# HDMI.net
KiCad netlist of a schematic drawn in Altium Designer
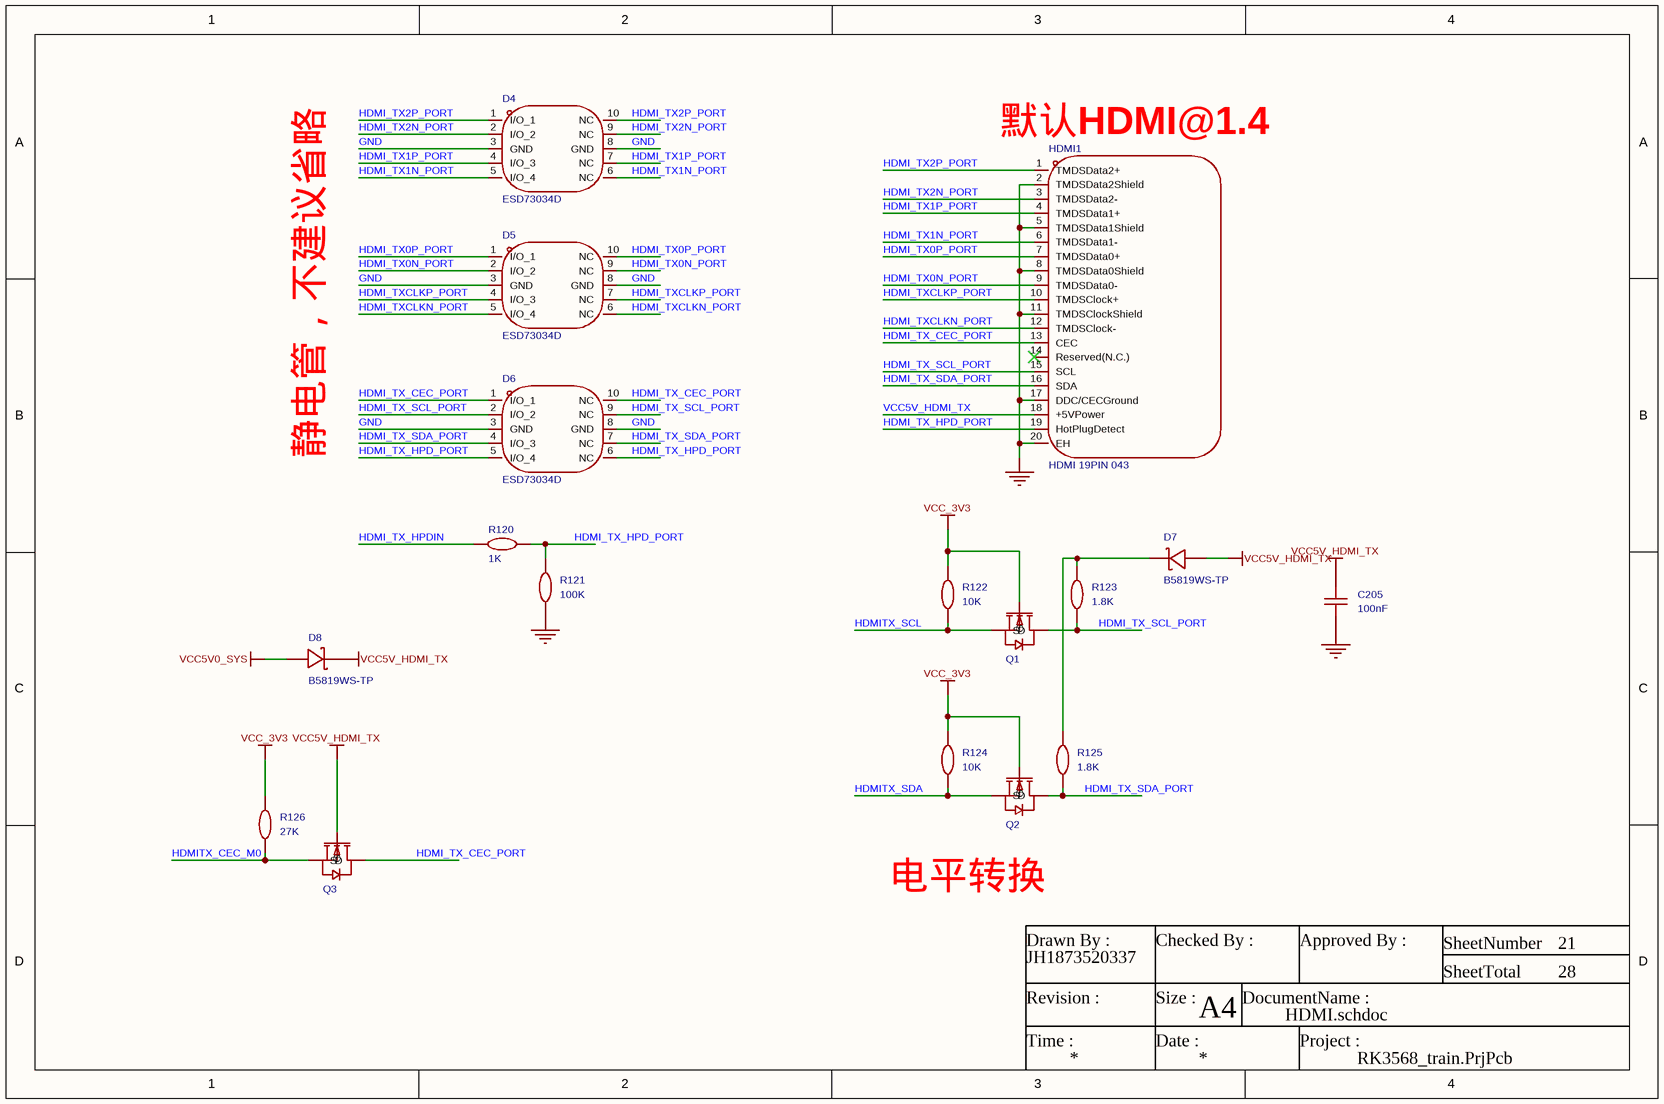
[diagram p0: HDMI.schdoc]

(export (version "E")
  (design (tool "Eeschema 10.0.6"))
  (components
    (comp (ref "C205")
      (value "100nF")
      (footprint "C0603")
      (libsource (lib "altium-import") (part "root_1_CAP_0603_"))
    )
    (comp (ref "D4")
      (value "ESD73034D")
      (footprint "DFN-10_L2.5-W1.0-P0.50-BL-2")
      (description "极性:双向;反向截止电压(Vrwm):3.3V;钳位电压:18V;峰值脉冲电流(Ipp):3A@8/20us;峰值脉冲功率(Ppp):60W@8/20us;击穿电压:8.5V;")
      (fields (field (name "MANUFACTURER") "TECH PUBLIC(台舟)"))
      (libsource (lib "altium-import") (part "root_0_ESD73034D_"))
    )
    (comp (ref "D5")
      (value "ESD73034D")
      (footprint "DFN-10_L2.5-W1.0-P0.50-BL-2")
      (description "极性:双向;反向截止电压(Vrwm):3.3V;钳位电压:18V;峰值脉冲电流(Ipp):3A@8/20us;峰值脉冲功率(Ppp):60W@8/20us;击穿电压:8.5V;")
      (fields (field (name "MANUFACTURER") "TECH PUBLIC(台舟)"))
      (libsource (lib "altium-import") (part "root_0_ESD73034D_"))
    )
    (comp (ref "D6")
      (value "ESD73034D")
      (footprint "DFN-10_L2.5-W1.0-P0.50-BL-2")
      (description "极性:双向;反向截止电压(Vrwm):3.3V;钳位电压:18V;峰值脉冲电流(Ipp):3A@8/20us;峰值脉冲功率(Ppp):60W@8/20us;击穿电压:8.5V;")
      (fields (field (name "MANUFACTURER") "TECH PUBLIC(台舟)"))
      (libsource (lib "altium-import") (part "root_0_ESD73034D_"))
    )
    (comp (ref "D7")
      (value "B5819WS-TP")
      (footprint "SOD-323_L1.8-W1.3-LS2.5-RD")
      (description "正向压降(Vf):600mV@1A;直流反向耐压(Vr):40V;平均整流电流(Io):1A;")
      (fields (field (name "MANUFACTURER") "MCC(美微科)"))
      (libsource (lib "altium-import") (part "root_0_B5819WS-TP_"))
    )
    (comp (ref "D8")
      (value "B5819WS-TP")
      (footprint "SOD-323_L1.8-W1.3-LS2.5-RD")
      (description "正向压降(Vf):600mV@1A;直流反向耐压(Vr):40V;平均整流电流(Io):1A;")
      (fields (field (name "MANUFACTURER") "MCC(美微科)"))
      (libsource (lib "altium-import") (part "root_2_B5819WS-TP_"))
    )
    (comp (ref "HDMI1")
      (value "HDMI 19PIN 043")
      (footprint "HDMI-SMD_HDMI-19PIN-043")
      (description "USB母座/HD-MI 19PIN母座 4脚插件 贴片19PIN 铁壳镀镍")
      (fields (field (name "MANUFACTURER") "SHOU HAN(首韩)"))
      (libsource (lib "altium-import") (part "root_0_HDMI 19PIN 043_"))
    )
    (comp (ref "Q1")
      (value "~")
      (footprint "SOT-23-3_L2.9-W1.3-P1.90-LS2.4-BR")
      (libsource (lib "altium-import") (part "root_3_AO3400A_N_"))
    )
    (comp (ref "Q2")
      (value "~")
      (footprint "SOT-23-3_L2.9-W1.3-P1.90-LS2.4-BR")
      (libsource (lib "altium-import") (part "root_3_AO3400A_N_"))
    )
    (comp (ref "Q3")
      (value "~")
      (footprint "SOT-23-3_L2.9-W1.3-P1.90-LS2.4-BR")
      (libsource (lib "altium-import") (part "root_3_AO3400A_N_"))
    )
    (comp (ref "R120")
      (value "1K")
      (footprint "R0402")
      (libsource (lib "altium-import") (part "root_0_Res_0402_"))
    )
    (comp (ref "R121")
      (value "100K")
      (footprint "R0402")
      (libsource (lib "altium-import") (part "root_1_Res_0402_"))
    )
    (comp (ref "R122")
      (value "10K")
      (footprint "R0402")
      (libsource (lib "altium-import") (part "root_1_Res_0402_"))
    )
    (comp (ref "R123")
      (value "1.8K")
      (footprint "R0402")
      (libsource (lib "altium-import") (part "root_1_Res_0402_"))
    )
    (comp (ref "R124")
      (value "10K")
      (footprint "R0402")
      (libsource (lib "altium-import") (part "root_1_Res_0402_"))
    )
    (comp (ref "R125")
      (value "1.8K")
      (footprint "R0402")
      (libsource (lib "altium-import") (part "root_1_Res_0402_"))
    )
    (comp (ref "R126")
      (value "27K")
      (footprint "R0402")
      (libsource (lib "altium-import") (part "root_1_Res_0402_"))
    )
  )
  (nets
    (net (code "1") (name "/HDMITX_CEC_M0") (class "Default")
      (node (ref "Q3") (pin "2") (pinfunction "S_2") (pintype "passive"))
      (node (ref "R126") (pin "1") (pinfunction "1_1") (pintype "passive"))
    )
    (net (code "2") (name "/HDMITX_SCL") (class "Default")
      (node (ref "Q1") (pin "2") (pinfunction "S_2") (pintype "passive"))
      (node (ref "R122") (pin "1") (pinfunction "1_1") (pintype "passive"))
    )
    (net (code "3") (name "/HDMITX_SDA") (class "Default")
      (node (ref "Q2") (pin "2") (pinfunction "S_2") (pintype "passive"))
      (node (ref "R124") (pin "1") (pinfunction "1_1") (pintype "passive"))
    )
    (net (code "4") (name "/HDMI_TX0N_PORT") (class "Default")
      (node (ref "D5") (pin "2") (pinfunction "I/O_2_2") (pintype "passive"))
      (node (ref "D5") (pin "9") (pinfunction "NC_9") (pintype "passive"))
      (node (ref "HDMI1") (pin "9") (pinfunction "TMDSData0-_9") (pintype "passive"))
    )
    (net (code "5") (name "/HDMI_TX0P_PORT") (class "Default")
      (node (ref "D5") (pin "1") (pinfunction "I/O_1_1") (pintype "passive"))
      (node (ref "D5") (pin "10") (pinfunction "NC_10") (pintype "passive"))
      (node (ref "HDMI1") (pin "7") (pinfunction "TMDSData0+_7") (pintype "passive"))
    )
    (net (code "6") (name "/HDMI_TX1N_PORT") (class "Default")
      (node (ref "D4") (pin "5") (pinfunction "I/O_4_5") (pintype "passive"))
      (node (ref "D4") (pin "6") (pinfunction "NC_6") (pintype "passive"))
      (node (ref "HDMI1") (pin "6") (pinfunction "TMDSData1-_6") (pintype "passive"))
    )
    (net (code "7") (name "/HDMI_TX1P_PORT") (class "Default")
      (node (ref "D4") (pin "4") (pinfunction "I/O_3_4") (pintype "passive"))
      (node (ref "D4") (pin "7") (pinfunction "NC_7") (pintype "passive"))
      (node (ref "HDMI1") (pin "4") (pinfunction "TMDSData1+_4") (pintype "passive"))
    )
    (net (code "8") (name "/HDMI_TX2N_PORT") (class "Default")
      (node (ref "D4") (pin "2") (pinfunction "I/O_2_2") (pintype "passive"))
      (node (ref "D4") (pin "9") (pinfunction "NC_9") (pintype "passive"))
      (node (ref "HDMI1") (pin "3") (pinfunction "TMDSData2-_3") (pintype "passive"))
    )
    (net (code "9") (name "/HDMI_TX2P_PORT") (class "Default")
      (node (ref "D4") (pin "1") (pinfunction "I/O_1_1") (pintype "passive"))
      (node (ref "D4") (pin "10") (pinfunction "NC_10") (pintype "passive"))
      (node (ref "HDMI1") (pin "1") (pinfunction "TMDSData2+_1") (pintype "passive"))
    )
    (net (code "10") (name "/HDMI_TXCLKN_PORT") (class "Default")
      (node (ref "D5") (pin "5") (pinfunction "I/O_4_5") (pintype "passive"))
      (node (ref "D5") (pin "6") (pinfunction "NC_6") (pintype "passive"))
      (node (ref "HDMI1") (pin "12") (pinfunction "TMDSClock-_12") (pintype "passive"))
    )
    (net (code "11") (name "/HDMI_TXCLKP_PORT") (class "Default")
      (node (ref "D5") (pin "4") (pinfunction "I/O_3_4") (pintype "passive"))
      (node (ref "D5") (pin "7") (pinfunction "NC_7") (pintype "passive"))
      (node (ref "HDMI1") (pin "10") (pinfunction "TMDSClock+_10") (pintype "passive"))
    )
    (net (code "12") (name "/HDMI_TX_CEC_PORT") (class "Default")
      (node (ref "D6") (pin "1") (pinfunction "I/O_1_1") (pintype "passive"))
      (node (ref "D6") (pin "10") (pinfunction "NC_10") (pintype "passive"))
      (node (ref "HDMI1") (pin "13") (pinfunction "CEC_13") (pintype "passive"))
      (node (ref "Q3") (pin "3") (pinfunction "D_3") (pintype "passive"))
    )
    (net (code "13") (name "/HDMI_TX_HPDIN") (class "Default")
      (node (ref "R120") (pin "1") (pinfunction "1_1") (pintype "passive"))
    )
    (net (code "14") (name "/HDMI_TX_HPD_PORT") (class "Default")
      (node (ref "D6") (pin "5") (pinfunction "I/O_4_5") (pintype "passive"))
      (node (ref "D6") (pin "6") (pinfunction "NC_6") (pintype "passive"))
      (node (ref "HDMI1") (pin "19") (pinfunction "HotPlugDetect_19") (pintype "passive"))
      (node (ref "R120") (pin "2") (pinfunction "2_2") (pintype "passive"))
      (node (ref "R121") (pin "2") (pinfunction "2_2") (pintype "passive"))
    )
    (net (code "15") (name "/HDMI_TX_SCL_PORT") (class "Default")
      (node (ref "D6") (pin "2") (pinfunction "I/O_2_2") (pintype "passive"))
      (node (ref "D6") (pin "9") (pinfunction "NC_9") (pintype "passive"))
      (node (ref "HDMI1") (pin "15") (pinfunction "SCL_15") (pintype "passive"))
      (node (ref "Q1") (pin "3") (pinfunction "D_3") (pintype "passive"))
      (node (ref "R123") (pin "1") (pinfunction "1_1") (pintype "passive"))
    )
    (net (code "16") (name "/HDMI_TX_SDA_PORT") (class "Default")
      (node (ref "D6") (pin "4") (pinfunction "I/O_3_4") (pintype "passive"))
      (node (ref "D6") (pin "7") (pinfunction "NC_7") (pintype "passive"))
      (node (ref "HDMI1") (pin "16") (pinfunction "SDA_16") (pintype "passive"))
      (node (ref "Q2") (pin "3") (pinfunction "D_3") (pintype "passive"))
      (node (ref "R125") (pin "1") (pinfunction "1_1") (pintype "passive"))
    )
    (net (code "17") (name "GND") (class "Default")
      (node (ref "C205") (pin "1") (pinfunction "1_1") (pintype "passive"))
      (node (ref "D4") (pin "3") (pinfunction "GND_3") (pintype "passive"))
      (node (ref "D4") (pin "8") (pinfunction "GND_8") (pintype "passive"))
      (node (ref "D5") (pin "3") (pinfunction "GND_3") (pintype "passive"))
      (node (ref "D5") (pin "8") (pinfunction "GND_8") (pintype "passive"))
      (node (ref "D6") (pin "3") (pinfunction "GND_3") (pintype "passive"))
      (node (ref "D6") (pin "8") (pinfunction "GND_8") (pintype "passive"))
      (node (ref "HDMI1") (pin "11") (pinfunction "TMDSClockShield_11") (pintype "passive"))
      (node (ref "HDMI1") (pin "17") (pinfunction "DDC/CECGround_17") (pintype "passive"))
      (node (ref "HDMI1") (pin "2") (pinfunction "TMDSData2Shield_2") (pintype "passive"))
      (node (ref "HDMI1") (pin "20") (pinfunction "EH_20") (pintype "passive"))
      (node (ref "HDMI1") (pin "5") (pinfunction "TMDSData1Shield_5") (pintype "passive"))
      (node (ref "HDMI1") (pin "8") (pinfunction "TMDSData0Shield_8") (pintype "passive"))
      (node (ref "R121") (pin "1") (pinfunction "1_1") (pintype "passive"))
    )
    (net (code "18") (name "Net-(D7-K)") (class "Default")
      (node (ref "D7") (pin "1") (pinfunction "K_1") (pintype "passive"))
      (node (ref "R123") (pin "2") (pinfunction "2_2") (pintype "passive"))
      (node (ref "R125") (pin "2") (pinfunction "2_2") (pintype "passive"))
    )
    (net (code "19") (name "VCC5V0_SYS") (class "Default")
      (node (ref "D8") (pin "2") (pinfunction "A_2") (pintype "passive"))
    )
    (net (code "20") (name "VCC5V_HDMI_TX") (class "Default")
      (node (ref "C205") (pin "2") (pinfunction "2_2") (pintype "passive"))
      (node (ref "D7") (pin "2") (pinfunction "A_2") (pintype "passive"))
      (node (ref "D8") (pin "1") (pinfunction "K_1") (pintype "passive"))
      (node (ref "HDMI1") (pin "18") (pinfunction "+5VPower_18") (pintype "passive"))
      (node (ref "Q3") (pin "1") (pinfunction "G_1") (pintype "passive"))
    )
    (net (code "21") (name "VCC_3V3") (class "Default")
      (node (ref "Q1") (pin "1") (pinfunction "G_1") (pintype "passive"))
      (node (ref "Q2") (pin "1") (pinfunction "G_1") (pintype "passive"))
      (node (ref "R122") (pin "2") (pinfunction "2_2") (pintype "passive"))
      (node (ref "R124") (pin "2") (pinfunction "2_2") (pintype "passive"))
      (node (ref "R126") (pin "2") (pinfunction "2_2") (pintype "passive"))
    )
    (net (code "22") (name "unconnected-(HDMI1-Reserved(N.C.)-Pad14)") (class "Default")
      (node (ref "HDMI1") (pin "14") (pinfunction "Reserved(N.C.)_14") (pintype "passive+no_connect"))
    )
  )
)
